# VESC_KS75600_power.net
KiCad netlist of a schematic drawn in Altium Designer
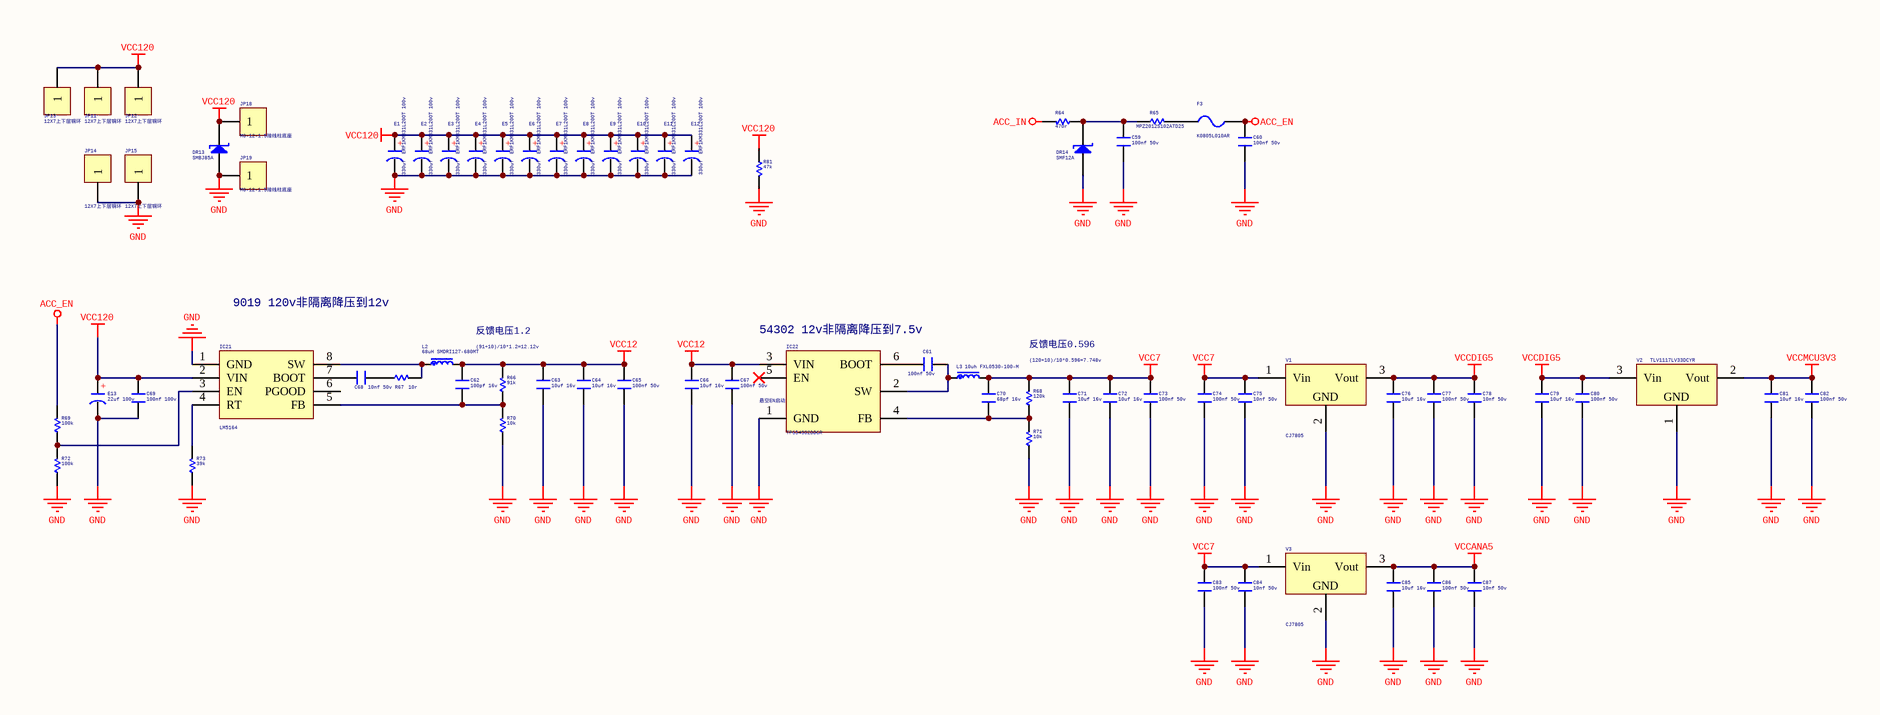
[diagram p0: VESC_KS75600_power.SchDoc]

(export (version "E")
  (design (tool "Eeschema 10.0.6"))
  (components
    (comp (ref "C59")
      (value "100nf 50v")
      (footprint "C 0805")
      (description "无极性贴片电容")
      (fields (field (name "VOLTAGE") "50v"))
      (libsource (lib "电阻-电容-电感") (part "C"))
    )
    (comp (ref "C60")
      (value "100nf 50v")
      (footprint "C 0805")
      (description "无极性贴片电容")
      (fields (field (name "VOLTAGE") "50v"))
      (libsource (lib "电阻-电容-电感") (part "C"))
    )
    (comp (ref "C61")
      (value "100nf 50v")
      (footprint "C 0805")
      (description "无极性贴片电容")
      (fields (field (name "VOLTAGE") "50v"))
      (libsource (lib "电阻-电容-电感") (part "C"))
    )
    (comp (ref "C62")
      (value "100pf 16v")
      (footprint "C 0603")
      (description "无极性贴片电容")
      (fields (field (name "VOLTAGE") "16v"))
      (libsource (lib "电阻-电容-电感") (part "C"))
    )
    (comp (ref "C63")
      (value "10uf 16v")
      (footprint "C 0805")
      (description "无极性贴片电容")
      (fields (field (name "VOLTAGE") "16v"))
      (libsource (lib "电阻-电容-电感") (part "C"))
    )
    (comp (ref "C64")
      (value "10uf 16v")
      (footprint "C 0805")
      (description "无极性贴片电容")
      (fields (field (name "VOLTAGE") "16v"))
      (libsource (lib "电阻-电容-电感") (part "C"))
    )
    (comp (ref "C65")
      (value "100nf 50v")
      (footprint "C 0805")
      (description "无极性贴片电容")
      (fields (field (name "VOLTAGE") "50v"))
      (libsource (lib "电阻-电容-电感") (part "C"))
    )
    (comp (ref "C66")
      (value "10uf 16v")
      (footprint "C 0805")
      (description "无极性贴片电容")
      (fields (field (name "VOLTAGE") "16v"))
      (libsource (lib "电阻-电容-电感") (part "C"))
    )
    (comp (ref "C67")
      (value "100nf 50v")
      (footprint "C 0805")
      (description "无极性贴片电容")
      (fields (field (name "VOLTAGE") "50v"))
      (libsource (lib "电阻-电容-电感") (part "C"))
    )
    (comp (ref "C68")
      (value "10nf 50v")
      (footprint "C 0603")
      (description "无极性贴片电容")
      (fields (field (name "VOLTAGE") "50v"))
      (libsource (lib "电阻-电容-电感") (part "C"))
    )
    (comp (ref "C69")
      (value "100nf 100v")
      (footprint "C 1206")
      (description "无极性贴片电容")
      (fields (field (name "VOLTAGE") "100v"))
      (libsource (lib "电阻-电容-电感") (part "C"))
    )
    (comp (ref "C70")
      (value "68pf 16v")
      (footprint "C 0603")
      (description "无极性贴片电容")
      (fields (field (name "VOLTAGE") "16v"))
      (libsource (lib "电阻-电容-电感") (part "C"))
    )
    (comp (ref "C71")
      (value "10uf 16v")
      (footprint "C 0805")
      (description "无极性贴片电容")
      (fields (field (name "VOLTAGE") "16v"))
      (libsource (lib "电阻-电容-电感") (part "C"))
    )
    (comp (ref "C72")
      (value "10uf 16v")
      (footprint "C 0805")
      (description "无极性贴片电容")
      (fields (field (name "VOLTAGE") "16v"))
      (libsource (lib "电阻-电容-电感") (part "C"))
    )
    (comp (ref "C73")
      (value "100nf 50v")
      (footprint "C 0805")
      (description "无极性贴片电容")
      (fields (field (name "VOLTAGE") "50v"))
      (libsource (lib "电阻-电容-电感") (part "C"))
    )
    (comp (ref "C74")
      (value "100nf 50v")
      (footprint "C 0603")
      (description "无极性贴片电容")
      (fields (field (name "VOLTAGE") "50v"))
      (libsource (lib "电阻-电容-电感") (part "C"))
    )
    (comp (ref "C75")
      (value "10nf 50v")
      (footprint "C 0603")
      (description "无极性贴片电容")
      (fields (field (name "VOLTAGE") "50v"))
      (libsource (lib "电阻-电容-电感") (part "C"))
    )
    (comp (ref "C76")
      (value "10uf 16v")
      (footprint "C 0805")
      (description "无极性贴片电容")
      (fields (field (name "VOLTAGE") "16v"))
      (libsource (lib "电阻-电容-电感") (part "C"))
    )
    (comp (ref "C77")
      (value "100nf 50v")
      (footprint "C 0603")
      (description "无极性贴片电容")
      (fields (field (name "VOLTAGE") "50v"))
      (libsource (lib "电阻-电容-电感") (part "C"))
    )
    (comp (ref "C78")
      (value "10nf 50v")
      (footprint "C 0603")
      (description "无极性贴片电容")
      (fields (field (name "VOLTAGE") "50v"))
      (libsource (lib "电阻-电容-电感") (part "C"))
    )
    (comp (ref "C79")
      (value "10uf 16v")
      (footprint "C 0805")
      (description "无极性贴片电容")
      (fields (field (name "VOLTAGE") "16v"))
      (libsource (lib "电阻-电容-电感") (part "C"))
    )
    (comp (ref "C80")
      (value "100nf 50v")
      (footprint "C 0603")
      (description "无极性贴片电容")
      (fields (field (name "VOLTAGE") "50v"))
      (libsource (lib "电阻-电容-电感") (part "C"))
    )
    (comp (ref "C81")
      (value "10uf 16v")
      (footprint "C 0805")
      (description "无极性贴片电容")
      (fields (field (name "VOLTAGE") "16v"))
      (libsource (lib "电阻-电容-电感") (part "C"))
    )
    (comp (ref "C82")
      (value "100nf 50v")
      (footprint "C 0603")
      (description "无极性贴片电容")
      (fields (field (name "VOLTAGE") "50v"))
      (libsource (lib "电阻-电容-电感") (part "C"))
    )
    (comp (ref "C83")
      (value "100nf 50v")
      (footprint "C 0603")
      (description "无极性贴片电容")
      (fields (field (name "VOLTAGE") "50v"))
      (libsource (lib "电阻-电容-电感") (part "C"))
    )
    (comp (ref "C84")
      (value "10nf 50v")
      (footprint "C 0603")
      (description "无极性贴片电容")
      (fields (field (name "VOLTAGE") "50v"))
      (libsource (lib "电阻-电容-电感") (part "C"))
    )
    (comp (ref "C85")
      (value "10uf 16v")
      (footprint "C 0805")
      (description "无极性贴片电容")
      (fields (field (name "VOLTAGE") "16v"))
      (libsource (lib "电阻-电容-电感") (part "C"))
    )
    (comp (ref "C86")
      (value "100nf 50v")
      (footprint "C 0603")
      (description "无极性贴片电容")
      (fields (field (name "VOLTAGE") "50v"))
      (libsource (lib "电阻-电容-电感") (part "C"))
    )
    (comp (ref "C87")
      (value "10nf 50v")
      (footprint "C 0603")
      (description "无极性贴片电容")
      (fields (field (name "VOLTAGE") "50v"))
      (libsource (lib "电阻-电容-电感") (part "C"))
    )
    (comp (ref "DR13")
      (value "SMBJ85A")
      (footprint "SMB")
      (description "瞬态电压抑制二极管(单向)")
      (libsource (lib "二极管-整流桥") (part "DR_S"))
    )
    (comp (ref "DR14")
      (value "SMF12A")
      (footprint "SOD-123F")
      (description "瞬态电压抑制二极管(单向)")
      (libsource (lib "二极管-整流桥") (part "DR_S"))
    )
    (comp (ref "E1")
      (value "330uf  ERF1KM331L20OT 100v")
      (footprint "CAP 7.5*16*25 - GD")
      (description "直插电解电容")
      (fields (field (name "VOLTAGE") "100v"))
      (libsource (lib "电阻-电容-电感") (part "C-CAP"))
    )
    (comp (ref "E2")
      (value "330uf  ERF1KM331L20OT 100v")
      (footprint "CAP 7.5*16*25 - GD")
      (description "直插电解电容")
      (fields (field (name "VOLTAGE") "100v"))
      (libsource (lib "电阻-电容-电感") (part "C-CAP"))
    )
    (comp (ref "E3")
      (value "330uf  ERF1KM331L20OT 100v")
      (footprint "CAP 7.5*16*25 - GD")
      (description "直插电解电容")
      (fields (field (name "VOLTAGE") "100v"))
      (libsource (lib "电阻-电容-电感") (part "C-CAP"))
    )
    (comp (ref "E4")
      (value "330uf  ERF1KM331L20OT 100v")
      (footprint "CAP 7.5*16*25 - GD")
      (description "直插电解电容")
      (fields (field (name "VOLTAGE") "100v"))
      (libsource (lib "电阻-电容-电感") (part "C-CAP"))
    )
    (comp (ref "E5")
      (value "330uf  ERF1KM331L20OT 100v")
      (footprint "CAP 7.5*16*25 - GD")
      (description "直插电解电容")
      (fields (field (name "VOLTAGE") "100v"))
      (libsource (lib "电阻-电容-电感") (part "C-CAP"))
    )
    (comp (ref "E6")
      (value "330uf  ERF1KM331L20OT 100v")
      (footprint "CAP 7.5*16*25 - GD")
      (description "直插电解电容")
      (fields (field (name "VOLTAGE") "100v"))
      (libsource (lib "电阻-电容-电感") (part "C-CAP"))
    )
    (comp (ref "E7")
      (value "330uf  ERF1KM331L20OT 100v")
      (footprint "CAP 7.5*16*25 - GD")
      (description "直插电解电容")
      (fields (field (name "VOLTAGE") "100v"))
      (libsource (lib "电阻-电容-电感") (part "C-CAP"))
    )
    (comp (ref "E8")
      (value "330uf  ERF1KM331L20OT 100v")
      (footprint "CAP 7.5*16*25 - GD")
      (description "直插电解电容")
      (fields (field (name "VOLTAGE") "100v"))
      (libsource (lib "电阻-电容-电感") (part "C-CAP"))
    )
    (comp (ref "E9")
      (value "330uf  ERF1KM331L20OT 100v")
      (footprint "CAP 7.5*16*25 - GD")
      (description "直插电解电容")
      (fields (field (name "VOLTAGE") "100v"))
      (libsource (lib "电阻-电容-电感") (part "C-CAP"))
    )
    (comp (ref "E10")
      (value "330uf  ERF1KM331L20OT 100v")
      (footprint "CAP 7.5*16*25 - GD")
      (description "直插电解电容")
      (fields (field (name "VOLTAGE") "100v"))
      (libsource (lib "电阻-电容-电感") (part "C-CAP"))
    )
    (comp (ref "E11")
      (value "330uf  ERF1KM331L20OT 100v")
      (footprint "CAP 7.5*16*25 - GD")
      (description "直插电解电容")
      (fields (field (name "VOLTAGE") "100v"))
      (libsource (lib "电阻-电容-电感") (part "C-CAP"))
    )
    (comp (ref "E12")
      (value "330uf  ERF1KM331L20OT 100v")
      (footprint "CAP 7.5*16*25 - GD")
      (description "直插电解电容")
      (fields (field (name "VOLTAGE") "100v"))
      (libsource (lib "电阻-电容-电感") (part "C-CAP"))
    )
    (comp (ref "E13")
      (value "22uf 100v")
      (footprint "CAP 2.5*6.3*11.2 - BK")
      (description "直插电解电容")
      (fields (field (name "VOLTAGE") "100v"))
      (libsource (lib "电阻-电容-电感") (part "C-CAP"))
    )
    (comp (ref "F3")
      (value "K0805L010AR")
      (footprint "FU 0805")
      (description "贴片保险丝")
      (libsource (lib "保险丝-晶振") (part "FU"))
    )
    (comp (ref "IC21")
      (value "LM5164")
      (footprint "SOP8_EPAD_L")
      (description "100V 1Mhz BUCK控制器")
      (libsource (lib "IC芯片") (part "MK9019"))
    )
    (comp (ref "IC22")
      (value "TPS54302DDCR")
      (footprint "SOT23-6L")
      (description "4.5V 至 28V 输入、3A 输出、EMI 友好型同步降压转换器")
      (libsource (lib "IC芯片") (part "TPS54302"))
    )
    (comp (ref "JP11")
      (value "12X7上下层铜环")
      (footprint "11x6.5上下层铜环")
      (description "1P接插件")
      (libsource (lib "") (part "Header 1_2"))
    )
    (comp (ref "JP12")
      (value "12X7上下层铜环")
      (footprint "11x6.5上下层铜环")
      (description "1P接插件")
      (libsource (lib "") (part "Header 1_2"))
    )
    (comp (ref "JP13")
      (value "12X7上下层铜环")
      (footprint "11x6.5上下层铜环")
      (description "1P接插件")
      (libsource (lib "") (part "Header 1_2"))
    )
    (comp (ref "JP14")
      (value "12X7上下层铜环")
      (footprint "11x6.5上下层铜环")
      (description "1P接插件")
      (libsource (lib "接插件") (part "Header 1"))
    )
    (comp (ref "JP15")
      (value "12X7上下层铜环")
      (footprint "11x6.5上下层铜环")
      (description "1P接插件")
      (libsource (lib "接插件") (part "Header 1"))
    )
    (comp (ref "JP18")
      (value "M6-12-1.5接线柱底座")
      (footprint "接线柱底座焊盘")
      (description "1P接插件")
      (libsource (lib "") (part "Header 1_1"))
    )
    (comp (ref "JP19")
      (value "M6-12-1.5接线柱底座")
      (footprint "接线柱底座焊盘")
      (description "1P接插件")
      (libsource (lib "") (part "Header 1_1"))
    )
    (comp (ref "L2")
      (value "68uH SMDRI127-680MT")
      (footprint "CDRH127")
      (description "功率屏蔽电感")
      (libsource (lib "电阻-电容-电感") (part "L-CDRH"))
    )
    (comp (ref "L3")
      (value "10uh FXL0530-100-M")
      (footprint "L-SMD-0530")
      (description "贴片一体成形功率电感")
      (libsource (lib "电阻-电容-电感") (part "L-SMD"))
    )
    (comp (ref "R64")
      (value "470r")
      (footprint "R 1206")
      (description "贴片电阻")
      (libsource (lib "电阻-电容-电感") (part "R"))
    )
    (comp (ref "R65")
      (value "MPZ2012S102ATD25")
      (footprint "R 0805")
      (description "贴片电阻")
      (libsource (lib "电阻-电容-电感") (part "R"))
    )
    (comp (ref "R66")
      (value "91k")
      (footprint "R 0603")
      (description "贴片电阻")
      (libsource (lib "电阻-电容-电感") (part "R"))
    )
    (comp (ref "R67")
      (value "10r")
      (footprint "R 1206-HP")
      (description "贴片电阻")
      (libsource (lib "电阻-电容-电感") (part "R"))
    )
    (comp (ref "R68")
      (value "120k")
      (footprint "R 0603")
      (description "贴片电阻")
      (libsource (lib "电阻-电容-电感") (part "R"))
    )
    (comp (ref "R69")
      (value "100k")
      (footprint "R 0805")
      (description "贴片电阻")
      (libsource (lib "电阻-电容-电感") (part "R"))
    )
    (comp (ref "R70")
      (value "10k")
      (footprint "R 0603")
      (description "贴片电阻")
      (libsource (lib "电阻-电容-电感") (part "R"))
    )
    (comp (ref "R71")
      (value "10k")
      (footprint "R 0603")
      (description "贴片电阻")
      (libsource (lib "电阻-电容-电感") (part "R"))
    )
    (comp (ref "R72")
      (value "100k")
      (footprint "R 0805")
      (description "贴片电阻")
      (libsource (lib "电阻-电容-电感") (part "R"))
    )
    (comp (ref "R73")
      (value "39k")
      (footprint "R 0805")
      (description "贴片电阻")
      (libsource (lib "电阻-电容-电感") (part "R"))
    )
    (comp (ref "R81")
      (value "47k")
      (footprint "R 2512")
      (description "贴片电阻")
      (libsource (lib "电阻-电容-电感") (part "R"))
    )
    (comp (ref "V1")
      (value "CJ7805")
      (footprint "TO252")
      (description "线性稳压芯片")
      (libsource (lib "IC芯片") (part "78xx"))
    )
    (comp (ref "V2")
      (value "TLV1117LV33DCYR")
      (footprint "SOT223_L")
      (description "三端稳压芯片")
      (libsource (lib "IC芯片") (part "AMS1117"))
    )
    (comp (ref "V3")
      (value "CJ7805")
      (footprint "TO252")
      (description "线性稳压芯片")
      (libsource (lib "IC芯片") (part "78xx"))
    )
  )
  (nets
    (net (code "1") (name "ACC_EN") (class "Default")
      (node (ref "C60") (pin "1") (pinfunction "1_1") (pintype "passive"))
      (node (ref "F3") (pin "1") (pinfunction "1_1") (pintype "passive"))
      (node (ref "R69") (pin "2") (pinfunction "2_2") (pintype "passive"))
    )
    (net (code "2") (name "ACC_IN") (class "Default")
      (node (ref "R64") (pin "2") (pinfunction "2_2") (pintype "passive"))
    )
    (net (code "3") (name "GND") (class "Default")
      (node (ref "C59") (pin "2") (pinfunction "2_2") (pintype "passive"))
      (node (ref "C60") (pin "2") (pinfunction "2_2") (pintype "passive"))
      (node (ref "C63") (pin "2") (pinfunction "2_2") (pintype "passive"))
      (node (ref "C64") (pin "2") (pinfunction "2_2") (pintype "passive"))
      (node (ref "C65") (pin "2") (pinfunction "2_2") (pintype "passive"))
      (node (ref "C66") (pin "2") (pinfunction "2_2") (pintype "passive"))
      (node (ref "C67") (pin "2") (pinfunction "2_2") (pintype "passive"))
      (node (ref "C69") (pin "1") (pinfunction "1_1") (pintype "passive"))
      (node (ref "C71") (pin "2") (pinfunction "2_2") (pintype "passive"))
      (node (ref "C72") (pin "2") (pinfunction "2_2") (pintype "passive"))
      (node (ref "C73") (pin "2") (pinfunction "2_2") (pintype "passive"))
      (node (ref "C74") (pin "2") (pinfunction "2_2") (pintype "passive"))
      (node (ref "C75") (pin "2") (pinfunction "2_2") (pintype "passive"))
      (node (ref "C76") (pin "1") (pinfunction "1_1") (pintype "passive"))
      (node (ref "C77") (pin "2") (pinfunction "2_2") (pintype "passive"))
      (node (ref "C78") (pin "2") (pinfunction "2_2") (pintype "passive"))
      (node (ref "C79") (pin "2") (pinfunction "2_2") (pintype "passive"))
      (node (ref "C80") (pin "2") (pinfunction "2_2") (pintype "passive"))
      (node (ref "C81") (pin "2") (pinfunction "2_2") (pintype "passive"))
      (node (ref "C82") (pin "2") (pinfunction "2_2") (pintype "passive"))
      (node (ref "C83") (pin "2") (pinfunction "2_2") (pintype "passive"))
      (node (ref "C84") (pin "2") (pinfunction "2_2") (pintype "passive"))
      (node (ref "C85") (pin "1") (pinfunction "1_1") (pintype "passive"))
      (node (ref "C86") (pin "2") (pinfunction "2_2") (pintype "passive"))
      (node (ref "C87") (pin "2") (pinfunction "2_2") (pintype "passive"))
      (node (ref "DR13") (pin "1") (pinfunction "A_1") (pintype "passive"))
      (node (ref "DR14") (pin "1") (pinfunction "A_1") (pintype "passive"))
      (node (ref "E1") (pin "2") (pinfunction "2_2") (pintype "passive"))
      (node (ref "E10") (pin "2") (pinfunction "2_2") (pintype "passive"))
      (node (ref "E11") (pin "2") (pinfunction "2_2") (pintype "passive"))
      (node (ref "E12") (pin "2") (pinfunction "2_2") (pintype "passive"))
      (node (ref "E13") (pin "2") (pinfunction "2_2") (pintype "passive"))
      (node (ref "E2") (pin "2") (pinfunction "2_2") (pintype "passive"))
      (node (ref "E3") (pin "2") (pinfunction "2_2") (pintype "passive"))
      (node (ref "E4") (pin "2") (pinfunction "2_2") (pintype "passive"))
      (node (ref "E5") (pin "2") (pinfunction "2_2") (pintype "passive"))
      (node (ref "E6") (pin "2") (pinfunction "2_2") (pintype "passive"))
      (node (ref "E7") (pin "2") (pinfunction "2_2") (pintype "passive"))
      (node (ref "E8") (pin "2") (pinfunction "2_2") (pintype "passive"))
      (node (ref "E9") (pin "2") (pinfunction "2_2") (pintype "passive"))
      (node (ref "IC21") (pin "1") (pinfunction "GND_1") (pintype "passive"))
      (node (ref "IC22") (pin "1") (pinfunction "GND_1") (pintype "passive"))
      (node (ref "JP14") (pin "1") (pinfunction "1_1") (pintype "passive"))
      (node (ref "JP15") (pin "1") (pinfunction "1_1") (pintype "passive"))
      (node (ref "JP19") (pin "1") (pinfunction "1_1") (pintype "passive"))
      (node (ref "R70") (pin "1") (pinfunction "1_1") (pintype "passive"))
      (node (ref "R71") (pin "1") (pinfunction "1_1") (pintype "passive"))
      (node (ref "R72") (pin "1") (pinfunction "1_1") (pintype "passive"))
      (node (ref "R73") (pin "1") (pinfunction "1_1") (pintype "passive"))
      (node (ref "R81") (pin "2") (pinfunction "2_2") (pintype "passive"))
      (node (ref "V1") (pin "2") (pinfunction "GND_2") (pintype "passive"))
      (node (ref "V2") (pin "1") (pinfunction "GND_1") (pintype "passive"))
      (node (ref "V3") (pin "2") (pinfunction "GND_2") (pintype "passive"))
    )
    (net (code "4") (name "Net-(C68-Pad1)") (class "Default")
      (node (ref "C68") (pin "1") (pinfunction "1_1") (pintype "passive"))
      (node (ref "R67") (pin "1") (pinfunction "1_1") (pintype "passive"))
    )
    (net (code "5") (name "Net-(DR14-K)") (class "Default")
      (node (ref "C59") (pin "1") (pinfunction "1_1") (pintype "passive"))
      (node (ref "DR14") (pin "2") (pinfunction "K_2") (pintype "passive"))
      (node (ref "R64") (pin "1") (pinfunction "1_1") (pintype "passive"))
      (node (ref "R65") (pin "1") (pinfunction "1_1") (pintype "passive"))
    )
    (net (code "6") (name "Net-(F3-Pad2)") (class "Default")
      (node (ref "F3") (pin "2") (pinfunction "2_2") (pintype "passive"))
      (node (ref "R65") (pin "2") (pinfunction "2_2") (pintype "passive"))
    )
    (net (code "7") (name "Net-(IC21-BOOT)") (class "Default")
      (node (ref "C68") (pin "2") (pinfunction "2_2") (pintype "passive"))
      (node (ref "IC21") (pin "7") (pinfunction "BOOT_7") (pintype "passive"))
    )
    (net (code "8") (name "Net-(IC21-EN)") (class "Default")
      (node (ref "IC21") (pin "3") (pinfunction "EN_3") (pintype "passive"))
      (node (ref "R69") (pin "1") (pinfunction "1_1") (pintype "passive"))
      (node (ref "R72") (pin "2") (pinfunction "2_2") (pintype "passive"))
    )
    (net (code "9") (name "Net-(IC21-FB)") (class "Default")
      (node (ref "C62") (pin "2") (pinfunction "2_2") (pintype "passive"))
      (node (ref "IC21") (pin "5") (pinfunction "FB_5") (pintype "passive"))
      (node (ref "R66") (pin "1") (pinfunction "1_1") (pintype "passive"))
      (node (ref "R70") (pin "2") (pinfunction "2_2") (pintype "passive"))
    )
    (net (code "10") (name "Net-(IC21-RT)") (class "Default")
      (node (ref "IC21") (pin "4") (pinfunction "RT_4") (pintype "passive"))
      (node (ref "R73") (pin "2") (pinfunction "2_2") (pintype "passive"))
    )
    (net (code "11") (name "Net-(IC21-SW)") (class "Default")
      (node (ref "IC21") (pin "8") (pinfunction "SW_8") (pintype "passive"))
      (node (ref "L2") (pin "1") (pinfunction "1_1") (pintype "passive"))
      (node (ref "R67") (pin "2") (pinfunction "2_2") (pintype "passive"))
    )
    (net (code "12") (name "Net-(IC22-BOOT)") (class "Default")
      (node (ref "C61") (pin "1") (pinfunction "1_1") (pintype "passive"))
      (node (ref "IC22") (pin "6") (pinfunction "BOOT_6") (pintype "passive"))
    )
    (net (code "13") (name "Net-(IC22-FB)") (class "Default")
      (node (ref "C70") (pin "2") (pinfunction "2_2") (pintype "passive"))
      (node (ref "IC22") (pin "4") (pinfunction "FB_4") (pintype "passive"))
      (node (ref "R68") (pin "1") (pinfunction "1_1") (pintype "passive"))
      (node (ref "R71") (pin "2") (pinfunction "2_2") (pintype "passive"))
    )
    (net (code "14") (name "Net-(IC22-SW)") (class "Default")
      (node (ref "C61") (pin "2") (pinfunction "2_2") (pintype "passive"))
      (node (ref "IC22") (pin "2") (pinfunction "SW_2") (pintype "passive"))
      (node (ref "L3") (pin "1") (pinfunction "1_1") (pintype "passive"))
    )
    (net (code "15") (name "VCC7") (class "Default")
      (node (ref "C70") (pin "1") (pinfunction "1_1") (pintype "passive"))
      (node (ref "C71") (pin "1") (pinfunction "1_1") (pintype "passive"))
      (node (ref "C72") (pin "1") (pinfunction "1_1") (pintype "passive"))
      (node (ref "C73") (pin "1") (pinfunction "1_1") (pintype "passive"))
      (node (ref "C74") (pin "1") (pinfunction "1_1") (pintype "passive"))
      (node (ref "C75") (pin "1") (pinfunction "1_1") (pintype "passive"))
      (node (ref "C83") (pin "1") (pinfunction "1_1") (pintype "passive"))
      (node (ref "C84") (pin "1") (pinfunction "1_1") (pintype "passive"))
      (node (ref "L3") (pin "2") (pinfunction "2_2") (pintype "passive"))
      (node (ref "R68") (pin "2") (pinfunction "2_2") (pintype "passive"))
      (node (ref "V1") (pin "1") (pinfunction "Vin_1") (pintype "passive"))
      (node (ref "V3") (pin "1") (pinfunction "Vin_1") (pintype "passive"))
    )
    (net (code "16") (name "VCC12") (class "Default")
      (node (ref "C62") (pin "1") (pinfunction "1_1") (pintype "passive"))
      (node (ref "C63") (pin "1") (pinfunction "1_1") (pintype "passive"))
      (node (ref "C64") (pin "1") (pinfunction "1_1") (pintype "passive"))
      (node (ref "C65") (pin "1") (pinfunction "1_1") (pintype "passive"))
      (node (ref "C66") (pin "1") (pinfunction "1_1") (pintype "passive"))
      (node (ref "C67") (pin "1") (pinfunction "1_1") (pintype "passive"))
      (node (ref "IC22") (pin "3") (pinfunction "VIN_3") (pintype "passive"))
      (node (ref "L2") (pin "2") (pinfunction "2_2") (pintype "passive"))
      (node (ref "R66") (pin "2") (pinfunction "2_2") (pintype "passive"))
    )
    (net (code "17") (name "VCC120") (class "Default")
      (node (ref "C69") (pin "2") (pinfunction "2_2") (pintype "passive"))
      (node (ref "DR13") (pin "2") (pinfunction "K_2") (pintype "passive"))
      (node (ref "E1") (pin "1") (pinfunction "1_1") (pintype "passive"))
      (node (ref "E10") (pin "1") (pinfunction "1_1") (pintype "passive"))
      (node (ref "E11") (pin "1") (pinfunction "1_1") (pintype "passive"))
      (node (ref "E12") (pin "1") (pinfunction "1_1") (pintype "passive"))
      (node (ref "E13") (pin "1") (pinfunction "1_1") (pintype "passive"))
      (node (ref "E2") (pin "1") (pinfunction "1_1") (pintype "passive"))
      (node (ref "E3") (pin "1") (pinfunction "1_1") (pintype "passive"))
      (node (ref "E4") (pin "1") (pinfunction "1_1") (pintype "passive"))
      (node (ref "E5") (pin "1") (pinfunction "1_1") (pintype "passive"))
      (node (ref "E6") (pin "1") (pinfunction "1_1") (pintype "passive"))
      (node (ref "E7") (pin "1") (pinfunction "1_1") (pintype "passive"))
      (node (ref "E8") (pin "1") (pinfunction "1_1") (pintype "passive"))
      (node (ref "E9") (pin "1") (pinfunction "1_1") (pintype "passive"))
      (node (ref "IC21") (pin "2") (pinfunction "VIN_2") (pintype "passive"))
      (node (ref "JP11") (pin "1") (pinfunction "1_1") (pintype "passive"))
      (node (ref "JP12") (pin "1") (pinfunction "1_1") (pintype "passive"))
      (node (ref "JP13") (pin "1") (pinfunction "1_1") (pintype "passive"))
      (node (ref "JP18") (pin "1") (pinfunction "1_1") (pintype "passive"))
      (node (ref "R81") (pin "1") (pinfunction "1_1") (pintype "passive"))
    )
    (net (code "18") (name "VCCANA5") (class "Default")
      (node (ref "C85") (pin "2") (pinfunction "2_2") (pintype "passive"))
      (node (ref "C86") (pin "1") (pinfunction "1_1") (pintype "passive"))
      (node (ref "C87") (pin "1") (pinfunction "1_1") (pintype "passive"))
      (node (ref "V3") (pin "3") (pinfunction "Vout_3") (pintype "passive"))
    )
    (net (code "19") (name "VCCDIG5") (class "Default")
      (node (ref "C76") (pin "2") (pinfunction "2_2") (pintype "passive"))
      (node (ref "C77") (pin "1") (pinfunction "1_1") (pintype "passive"))
      (node (ref "C78") (pin "1") (pinfunction "1_1") (pintype "passive"))
      (node (ref "C79") (pin "1") (pinfunction "1_1") (pintype "passive"))
      (node (ref "C80") (pin "1") (pinfunction "1_1") (pintype "passive"))
      (node (ref "V1") (pin "3") (pinfunction "Vout_3") (pintype "passive"))
      (node (ref "V2") (pin "3") (pinfunction "Vin_3") (pintype "passive"))
    )
    (net (code "20") (name "VCCMCU3V3") (class "Default")
      (node (ref "C81") (pin "1") (pinfunction "1_1") (pintype "passive"))
      (node (ref "C82") (pin "1") (pinfunction "1_1") (pintype "passive"))
      (node (ref "V2") (pin "2") (pinfunction "Vout_2") (pintype "passive"))
    )
    (net (code "21") (name "unconnected-(IC21-PGOOD-Pad6)") (class "Default")
      (node (ref "IC21") (pin "6") (pinfunction "PGOOD_6") (pintype "passive"))
    )
    (net (code "22") (name "unconnected-(IC22-EN-Pad5)") (class "Default")
      (node (ref "IC22") (pin "5") (pinfunction "EN_5") (pintype "passive+no_connect"))
    )
  )
)
